# BalconyLight.net
KiCad netlist of a schematic drawn in EAGLE
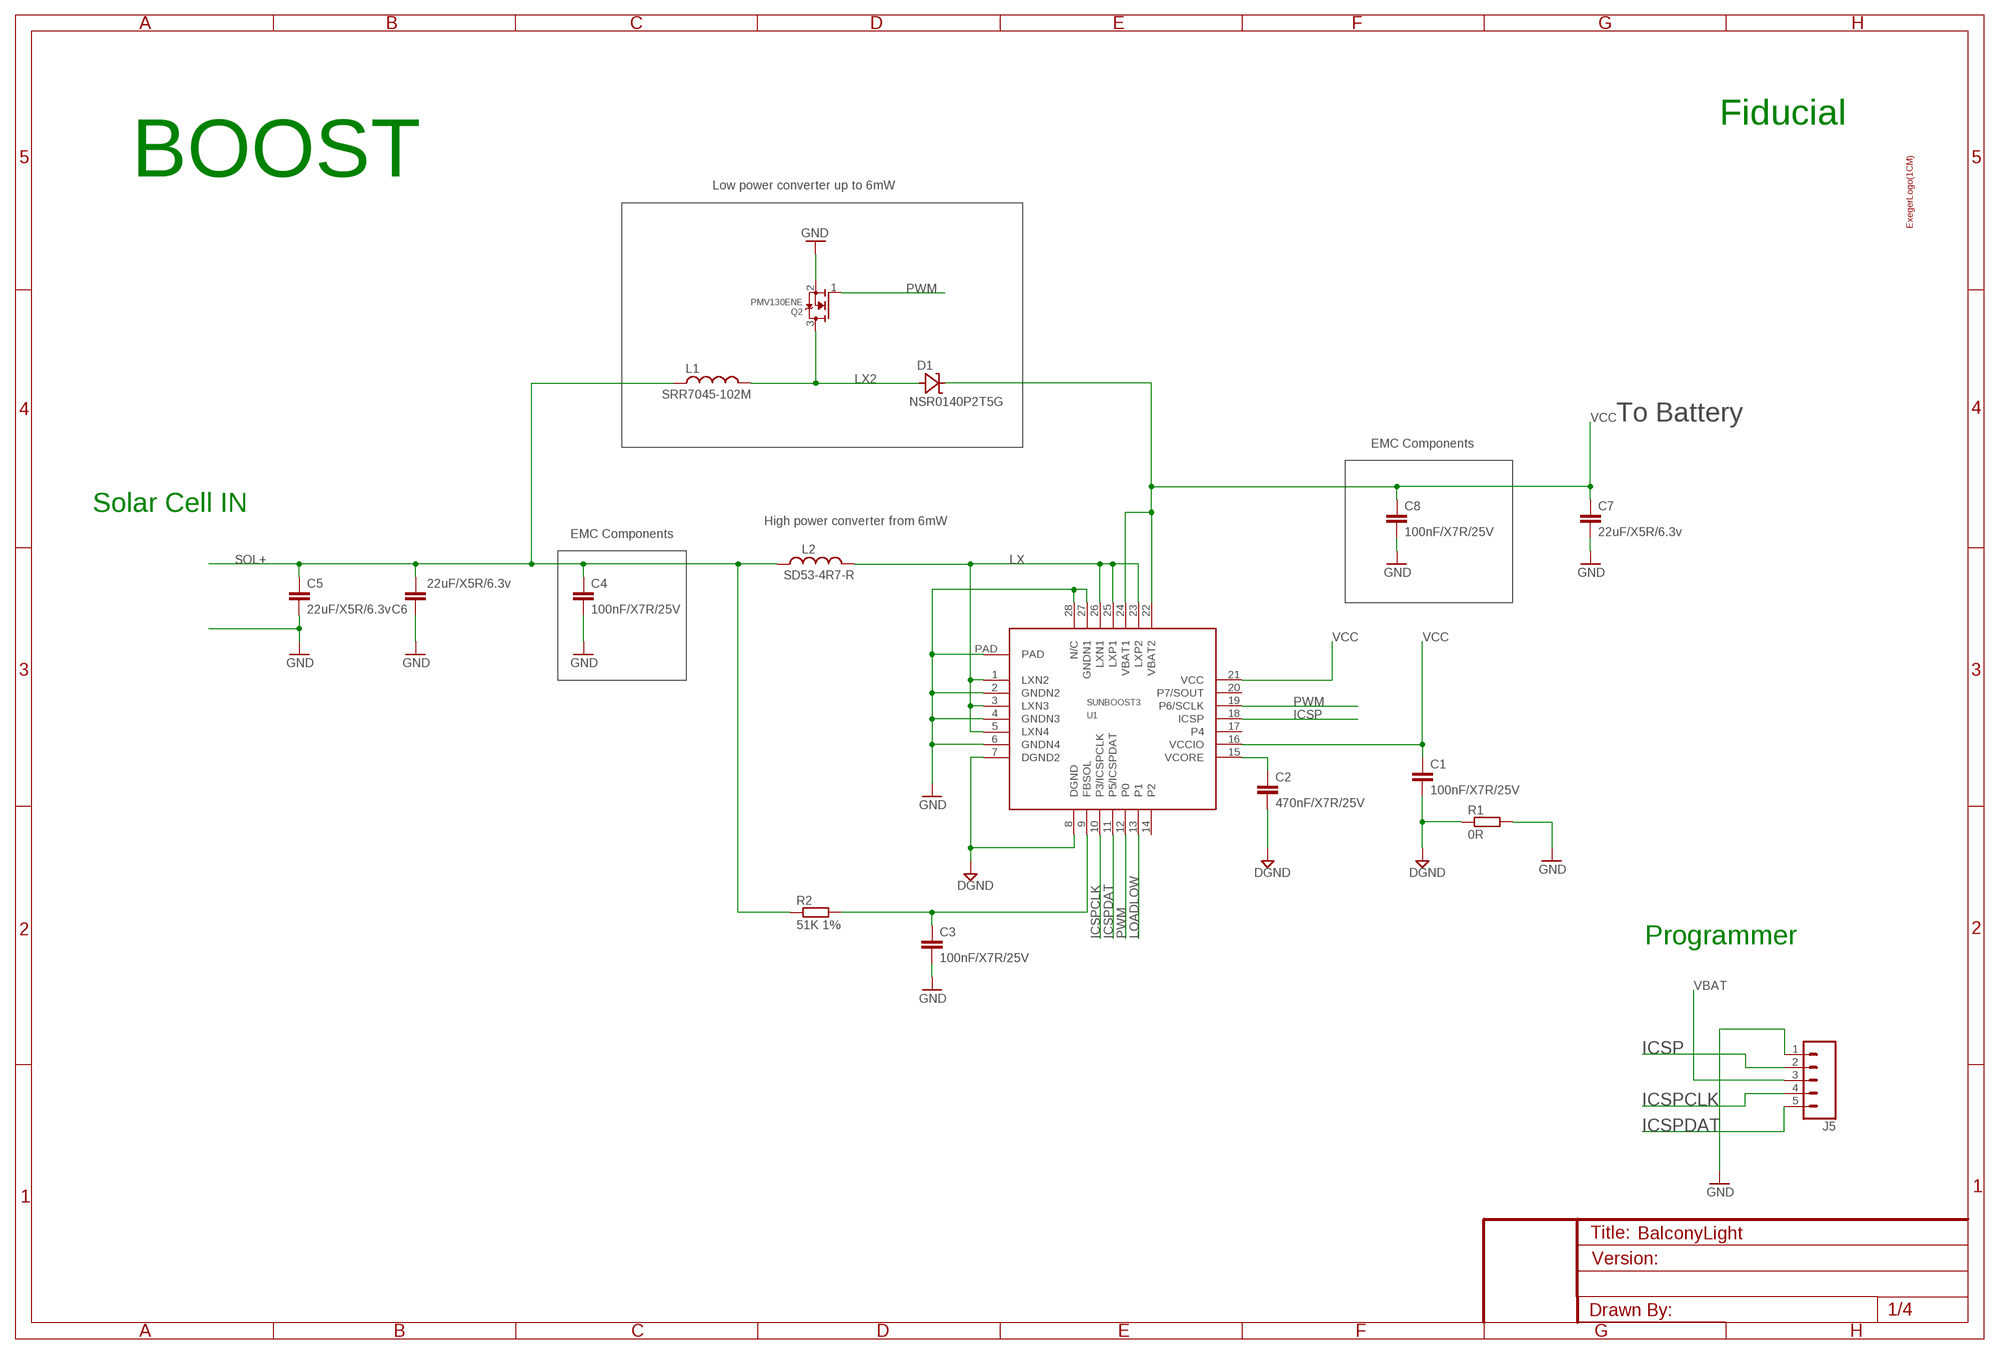
[diagram p0: schematic, sheet 1]
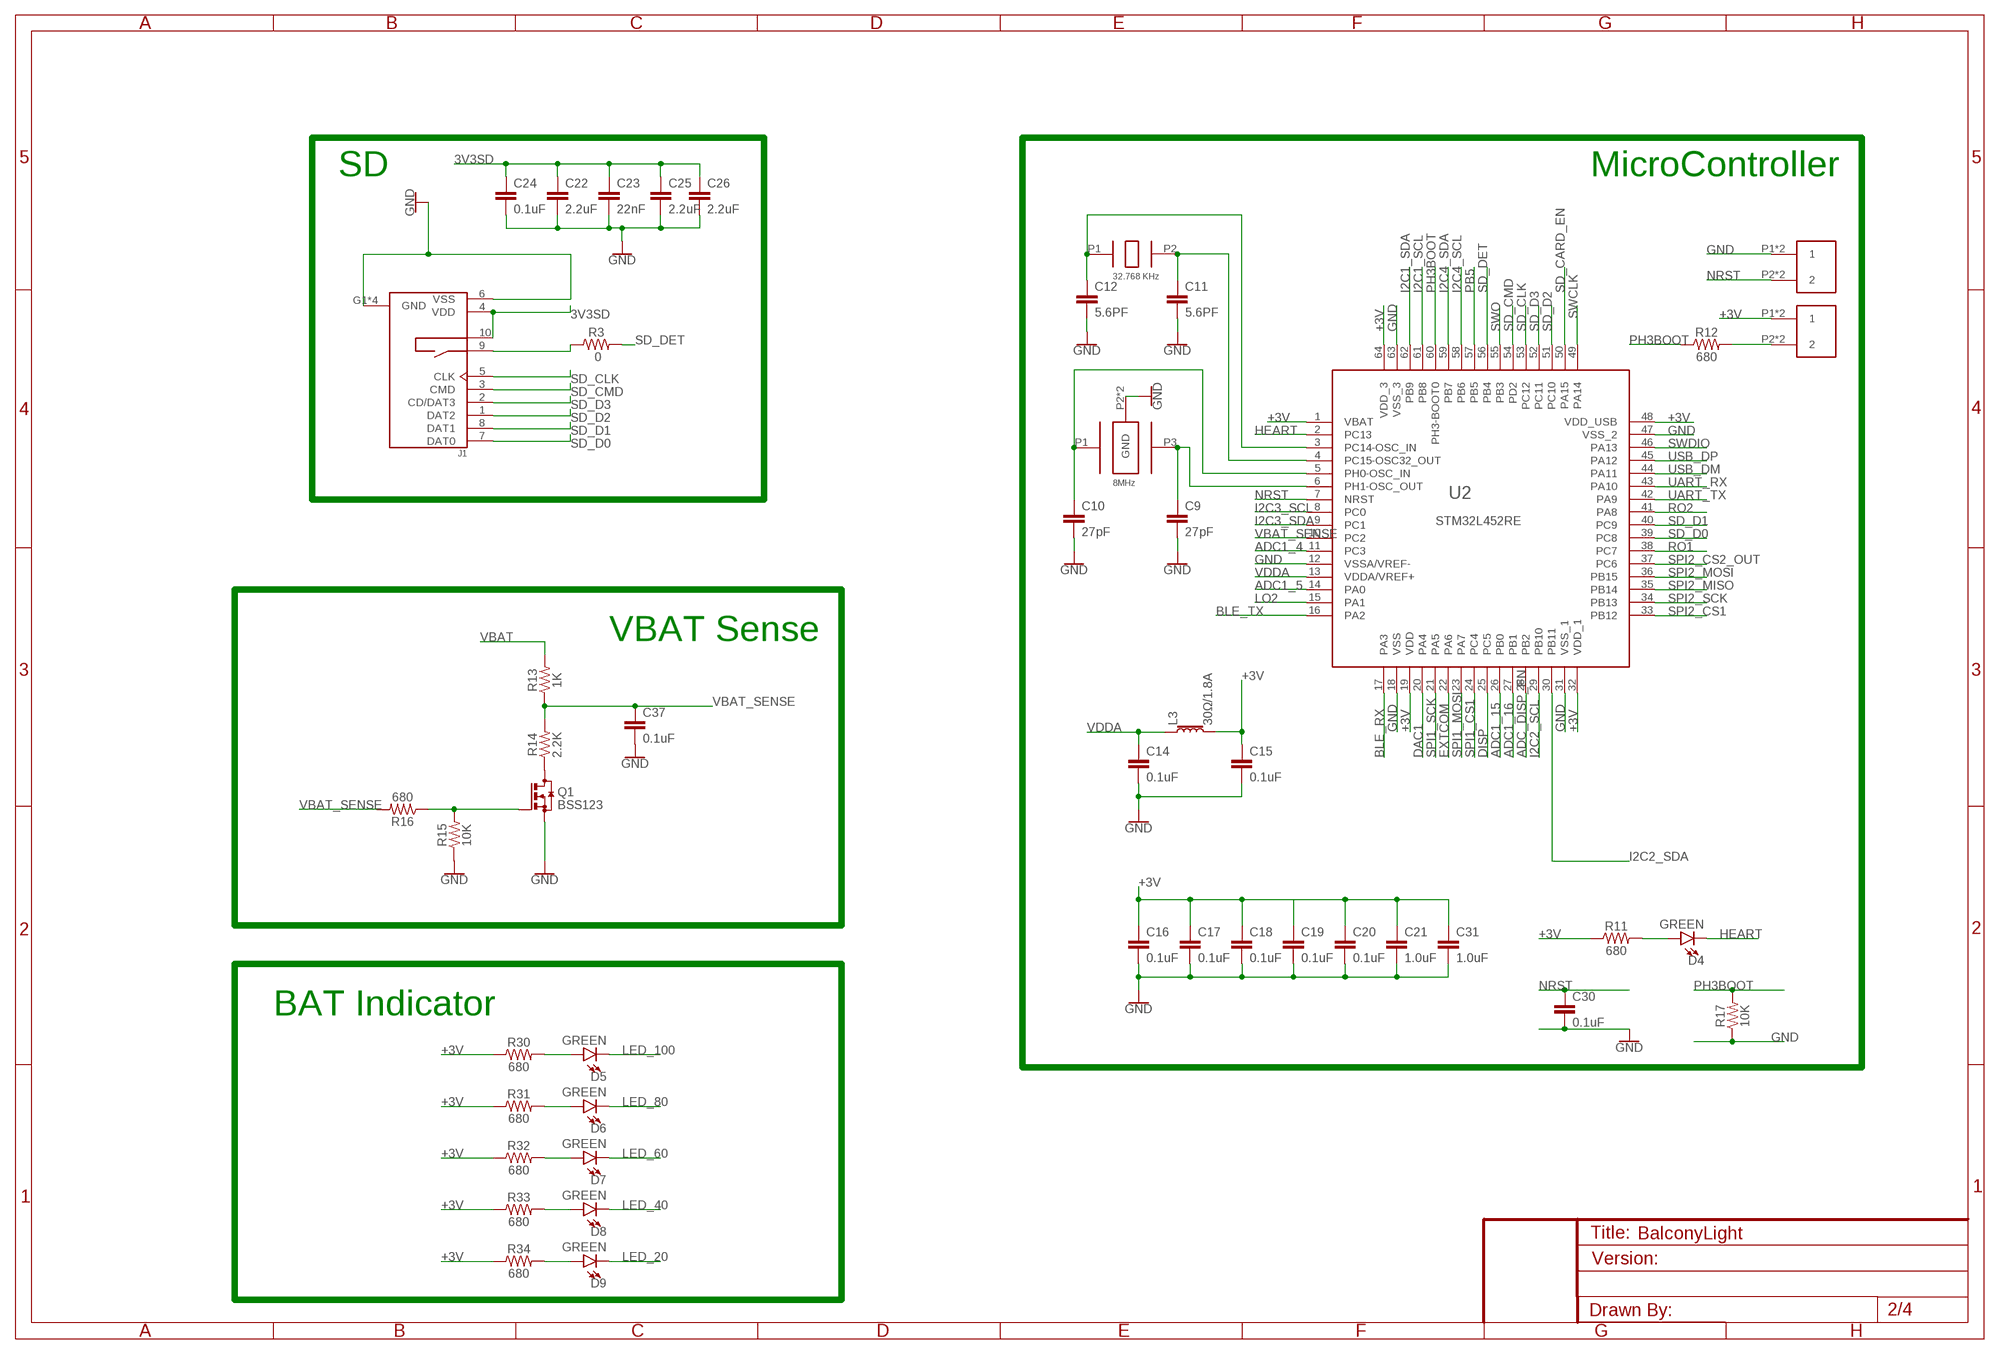
[diagram p1: schematic, sheet 2]
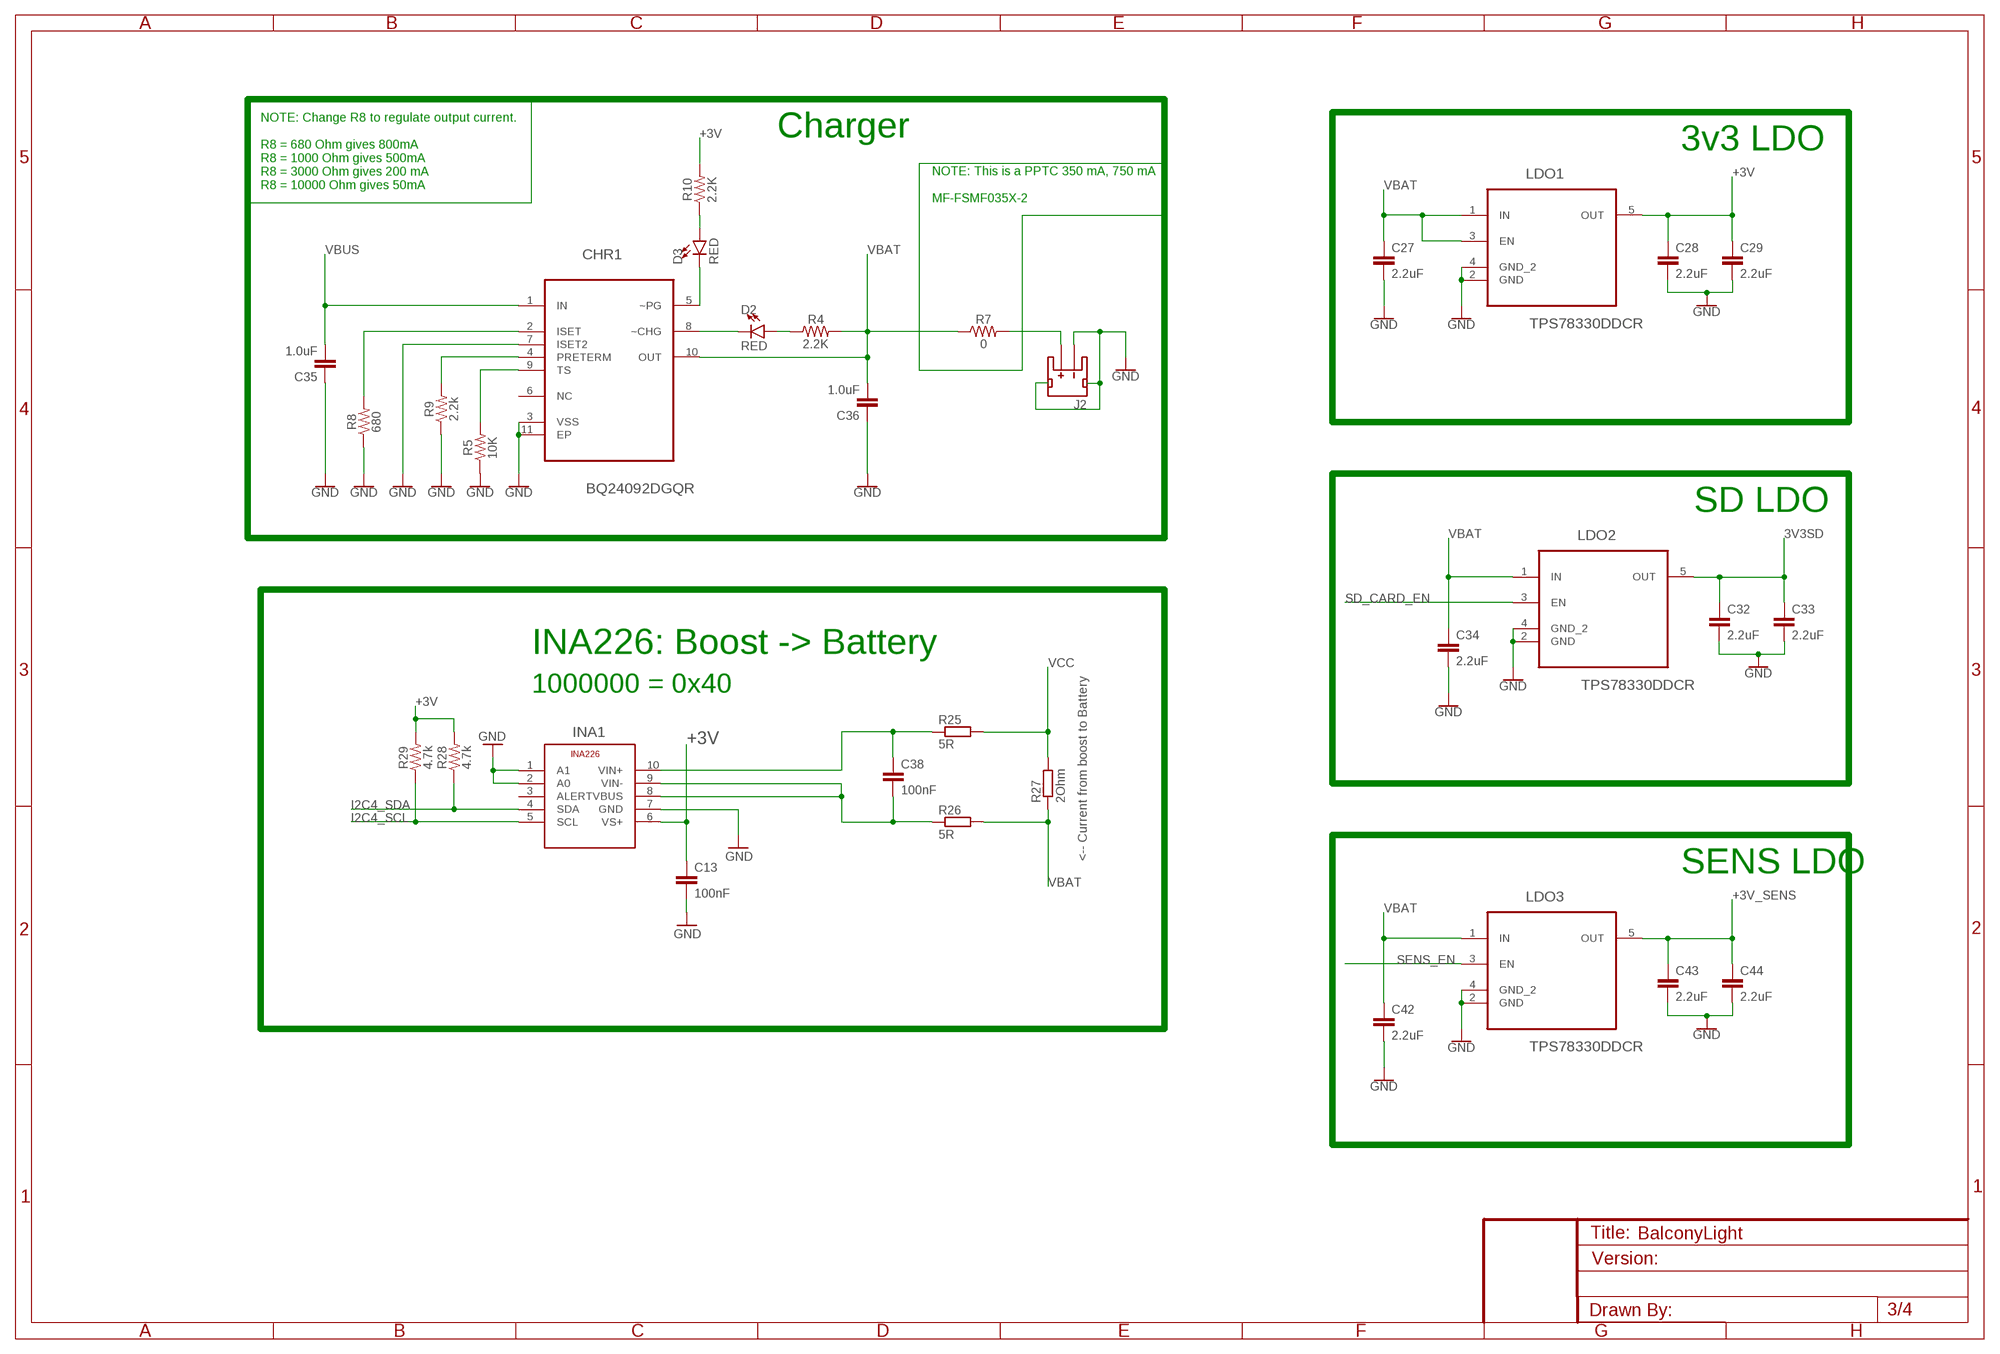
[diagram p2: schematic, sheet 3]
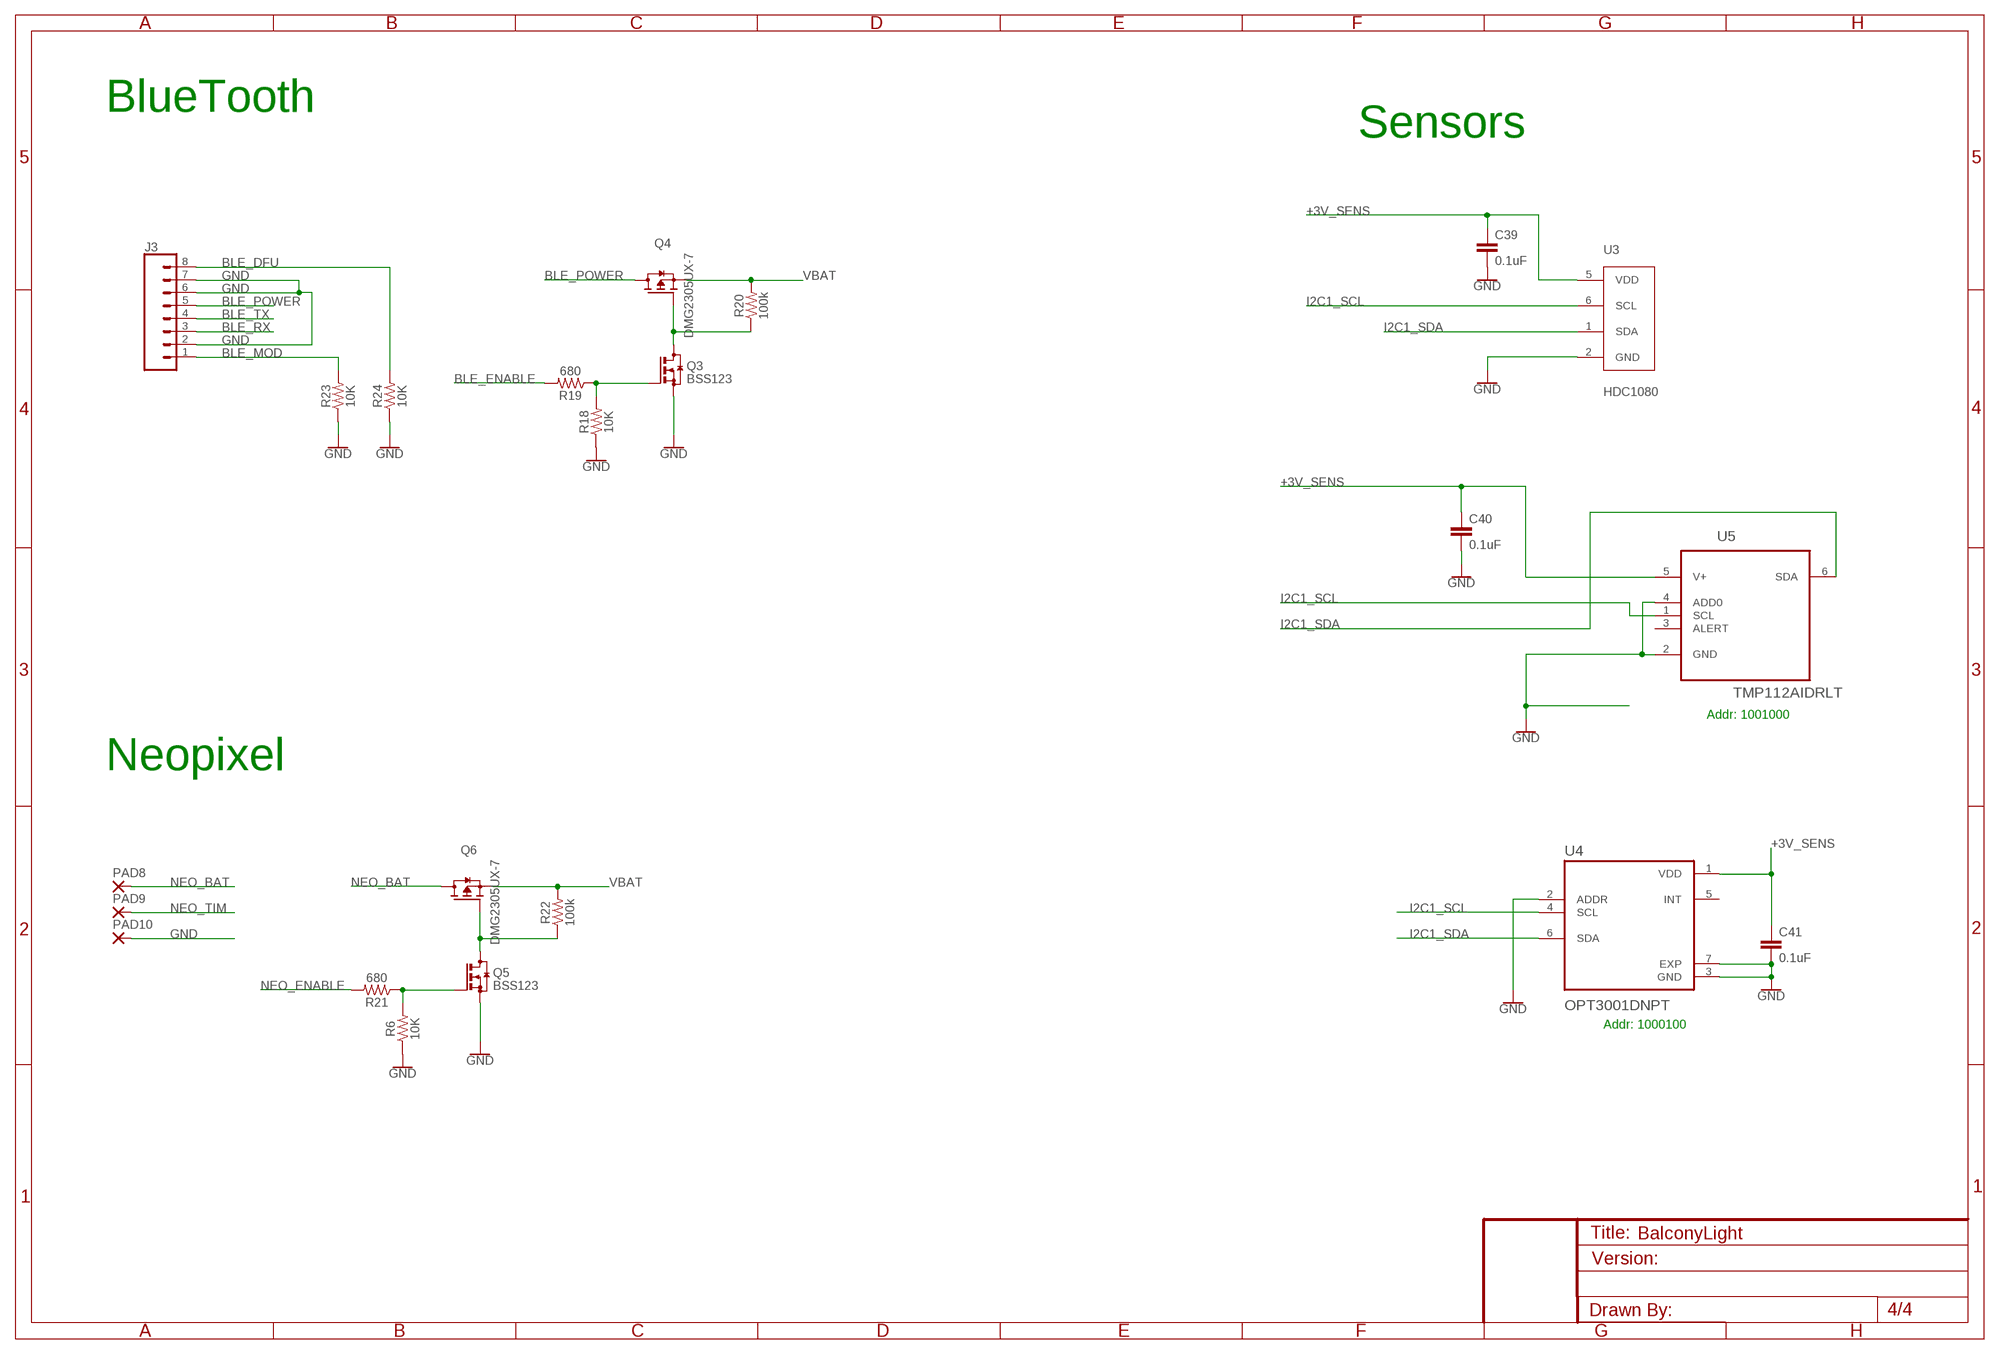
[diagram p3: schematic, sheet 4]

(export (version "E")
  (design (tool "Eeschema 10.0.6"))
  (components
    (comp (ref "C13")
      (value "100nF")
      (footprint "eagle-import:C0402")
      (libsource (lib "eagle-import") (part "C-EUC0402"))
    )
    (comp (ref "C27")
      (value "2.2uF")
      (footprint "eagle-import:0603")
      (libsource (lib "eagle-import") (part "2.2UF-0603-10V-20%"))
    )
    (comp (ref "C28")
      (value "2.2uF")
      (footprint "eagle-import:0603")
      (libsource (lib "eagle-import") (part "2.2UF-0603-10V-20%"))
    )
    (comp (ref "C29")
      (value "2.2uF")
      (footprint "eagle-import:0603")
      (libsource (lib "eagle-import") (part "2.2UF-0603-10V-20%"))
    )
    (comp (ref "C32")
      (value "2.2uF")
      (footprint "eagle-import:0603")
      (libsource (lib "eagle-import") (part "2.2UF-0603-10V-20%"))
    )
    (comp (ref "C33")
      (value "2.2uF")
      (footprint "eagle-import:0603")
      (libsource (lib "eagle-import") (part "2.2UF-0603-10V-20%"))
    )
    (comp (ref "C34")
      (value "2.2uF")
      (footprint "eagle-import:0603")
      (libsource (lib "eagle-import") (part "2.2UF-0603-10V-20%"))
    )
    (comp (ref "C35")
      (value "1.0uF")
      (footprint "eagle-import:0603")
      (libsource (lib "eagle-import") (part "1.0UF-0603-16V-10%"))
    )
    (comp (ref "C36")
      (value "1.0uF")
      (footprint "eagle-import:0603")
      (libsource (lib "eagle-import") (part "1.0UF-0603-16V-10%"))
    )
    (comp (ref "C38")
      (value "100nF")
      (footprint "eagle-import:C0402")
      (libsource (lib "eagle-import") (part "C-EUC0402"))
    )
    (comp (ref "C42")
      (value "2.2uF")
      (footprint "eagle-import:0603")
      (libsource (lib "eagle-import") (part "2.2UF-0603-10V-20%"))
    )
    (comp (ref "C43")
      (value "2.2uF")
      (footprint "eagle-import:0603")
      (libsource (lib "eagle-import") (part "2.2UF-0603-10V-20%"))
    )
    (comp (ref "C44")
      (value "2.2uF")
      (footprint "eagle-import:0603")
      (libsource (lib "eagle-import") (part "2.2UF-0603-10V-20%"))
    )
    (comp (ref "CHR1")
      (value "BQ24092DGQR")
      (footprint "eagle-import:SOP50P490X110-11N")
      (fields (field (name "MF") "Texas Instruments"))
      (libsource (lib "eagle-import") (part "BQ24092DGQR"))
    )
    (comp (ref "D2")
      (value "RED")
      (footprint "eagle-import:LED-0603")
      (libsource (lib "eagle-import") (part "LED-RED0603"))
    )
    (comp (ref "D3")
      (value "RED")
      (footprint "eagle-import:LED-0603")
      (libsource (lib "eagle-import") (part "LED-RED0603"))
    )
    (comp (ref "INA1")
      (value "TI-INA226")
      (footprint "eagle-import:TI-INA226")
      (libsource (lib "eagle-import") (part "TI-INA226"))
    )
    (comp (ref "J2")
      (value "JST_2MM_MALE")
      (footprint "eagle-import:JST-2-SMD")
      (libsource (lib "eagle-import") (part "JST_2MM_MALE"))
    )
    (comp (ref "LDO1")
      (value "TPS78330DDCR")
      (footprint "eagle-import:SOT95P280X110-5N")
      (fields (field (name "MF") "Texas Instruments"))
      (libsource (lib "eagle-import") (part "TPS78330DDCR"))
    )
    (comp (ref "LDO2")
      (value "TPS78330DDCR")
      (footprint "eagle-import:SOT95P280X110-5N")
      (fields (field (name "MF") "Texas Instruments"))
      (libsource (lib "eagle-import") (part "TPS78330DDCR"))
    )
    (comp (ref "LDO3")
      (value "TPS78330DDCR")
      (footprint "eagle-import:SOT95P280X110-5N")
      (fields (field (name "MF") "Texas Instruments"))
      (libsource (lib "eagle-import") (part "TPS78330DDCR"))
    )
    (comp (ref "R4")
      (value "2.2K")
      (footprint "eagle-import:0402")
      (libsource (lib "eagle-import") (part "100KOHM-0402-1/16W-1%"))
    )
    (comp (ref "R5")
      (value "10K")
      (footprint "eagle-import:0402")
      (libsource (lib "eagle-import") (part "100KOHM-0402-1/16W-1%"))
    )
    (comp (ref "R7")
      (value "0")
      (footprint "eagle-import:0603")
      (libsource (lib "eagle-import") (part "0OHM-0603-1/10W-5%"))
    )
    (comp (ref "R8")
      (value "680")
      (footprint "eagle-import:0402")
      (libsource (lib "eagle-import") (part "100KOHM-0402-1/16W-1%"))
    )
    (comp (ref "R9")
      (value "2.2k")
      (footprint "eagle-import:0402")
      (libsource (lib "eagle-import") (part "100KOHM-0402-1/16W-1%"))
    )
    (comp (ref "R10")
      (value "2.2K")
      (footprint "eagle-import:0402")
      (libsource (lib "eagle-import") (part "100KOHM-0402-1/16W-1%"))
    )
    (comp (ref "R25")
      (value "5R")
      (footprint "eagle-import:R0402")
      (libsource (lib "eagle-import") (part "R-EU_R0402"))
    )
    (comp (ref "R26")
      (value "5R")
      (footprint "eagle-import:R0402")
      (libsource (lib "eagle-import") (part "R-EU_R0402"))
    )
    (comp (ref "R27")
      (value "2Ohm")
      (footprint "eagle-import:R0603")
      (libsource (lib "eagle-import") (part "R-EU_R0603"))
    )
    (comp (ref "R28")
      (value "4.7k")
      (footprint "eagle-import:0603")
      (libsource (lib "eagle-import") (part "4.7KOHM-0603-1/10W-1%"))
    )
    (comp (ref "R29")
      (value "4.7k")
      (footprint "eagle-import:0603")
      (libsource (lib "eagle-import") (part "4.7KOHM-0603-1/10W-1%"))
    )
    (comp (ref "C1")
      (value "100nF/X7R/25V")
      (footprint "eagle-import:C0402")
      (libsource (lib "eagle-import") (part "C-EUC0402"))
    )
    (comp (ref "C2")
      (value "470nF/X7R/25V")
      (footprint "eagle-import:C0402")
      (libsource (lib "eagle-import") (part "C-EUC0402"))
    )
    (comp (ref "C3")
      (value "100nF/X7R/25V")
      (footprint "eagle-import:C0402")
      (libsource (lib "eagle-import") (part "C-EUC0402"))
    )
    (comp (ref "C4")
      (value "100nF/X7R/25V")
      (footprint "eagle-import:C0402")
      (libsource (lib "eagle-import") (part "C-EUC0402"))
    )
    (comp (ref "C5")
      (value "22uF/X5R/6.3v")
      (footprint "eagle-import:C0805")
      (libsource (lib "eagle-import") (part "C-EUC0805"))
    )
    (comp (ref "C6")
      (value "22uF/X5R/6.3v")
      (footprint "eagle-import:C0805")
      (libsource (lib "eagle-import") (part "C-EUC0805"))
    )
    (comp (ref "C7")
      (value "22uF/X5R/6.3v")
      (footprint "eagle-import:C0805")
      (libsource (lib "eagle-import") (part "C-EUC0805"))
    )
    (comp (ref "C8")
      (value "100nF/X7R/25V")
      (footprint "eagle-import:C0402")
      (libsource (lib "eagle-import") (part "C-EUC0402"))
    )
    (comp (ref "D1")
      (value "NSR0140P2T5G")
      (footprint "eagle-import:SODFL1006X40N")
      (libsource (lib "eagle-import") (part "NSR0140P2T5G"))
    )
    (comp (ref "J5")
      (value "CONN_05LOCK")
      (footprint "eagle-import:1X05_LOCK")
      (libsource (lib "eagle-import") (part "CONN_05LOCK"))
    )
    (comp (ref "L1")
      (value "SRR7045-102M")
      (footprint "eagle-import:SRR7045")
      (libsource (lib "eagle-import") (part "SRR7045-102M"))
    )
    (comp (ref "L2")
      (value "SD53-4R7-R")
      (footprint "eagle-import:SD53")
      (libsource (lib "eagle-import") (part "SD53-4R7-R"))
    )
    (comp (ref "Q2")
      (value "PMV130ENE")
      (footprint "eagle-import:SOT23")
      (libsource (lib "eagle-import") (part "MOSFET-NREFLOW"))
    )
    (comp (ref "R1")
      (value "0R")
      (footprint "eagle-import:R0402")
      (libsource (lib "eagle-import") (part "resistor_R-EU_R0402"))
    )
    (comp (ref "R2")
      (value "51K 1%")
      (footprint "eagle-import:R0402")
      (libsource (lib "eagle-import") (part "resistor_R-EU_R0402"))
    )
    (comp (ref "U$13")
      (value "EXEGER_LOGO_1CM")
      (footprint "eagle-import:EXEGER_LOGO_1CM")
      (libsource (lib "eagle-import") (part "EXEGER_LOGO_1CM"))
    )
    (comp (ref "U1")
      (value "SUNBOOST3")
      (footprint "eagle-import:QFN-28-4X4")
      (libsource (lib "eagle-import") (part "SUNBOOST3"))
    )
    (comp (ref "C9")
      (value "27pF")
      (footprint "eagle-import:0402")
      (libsource (lib "eagle-import") (part "0.8PF-0402-50V-0.1PF"))
    )
    (comp (ref "C10")
      (value "27pF")
      (footprint "eagle-import:0402")
      (libsource (lib "eagle-import") (part "0.8PF-0402-50V-0.1PF"))
    )
    (comp (ref "C11")
      (value "5.6PF")
      (footprint "eagle-import:0603")
      (libsource (lib "eagle-import") (part "5.6PF-0603-50V-5%"))
    )
    (comp (ref "C12")
      (value "5.6PF")
      (footprint "eagle-import:0603")
      (libsource (lib "eagle-import") (part "5.6PF-0603-50V-5%"))
    )
    (comp (ref "C14")
      (value "0.1uF")
      (footprint "eagle-import:0402")
      (libsource (lib "eagle-import") (part "0.1UF-0402-16V-10%"))
    )
    (comp (ref "C15")
      (value "0.1uF")
      (footprint "eagle-import:0402")
      (libsource (lib "eagle-import") (part "0.1UF-0402-16V-10%"))
    )
    (comp (ref "C16")
      (value "0.1uF")
      (footprint "eagle-import:0402")
      (libsource (lib "eagle-import") (part "0.1UF-0402-16V-10%"))
    )
    (comp (ref "C17")
      (value "0.1uF")
      (footprint "eagle-import:0402")
      (libsource (lib "eagle-import") (part "0.1UF-0402-16V-10%"))
    )
    (comp (ref "C18")
      (value "0.1uF")
      (footprint "eagle-import:0402")
      (libsource (lib "eagle-import") (part "0.1UF-0402-16V-10%"))
    )
    (comp (ref "C19")
      (value "0.1uF")
      (footprint "eagle-import:0402")
      (libsource (lib "eagle-import") (part "0.1UF-0402-16V-10%"))
    )
    (comp (ref "C20")
      (value "0.1uF")
      (footprint "eagle-import:0402")
      (libsource (lib "eagle-import") (part "0.1UF-0402-16V-10%"))
    )
    (comp (ref "C21")
      (value "1.0uF")
      (footprint "eagle-import:0603")
      (libsource (lib "eagle-import") (part "1.0UF-0603-16V-10%"))
    )
    (comp (ref "C22")
      (value "2.2uF")
      (footprint "eagle-import:0603")
      (libsource (lib "eagle-import") (part "2.2UF-0603-10V-20%"))
    )
    (comp (ref "C23")
      (value "22nF")
      (footprint "eagle-import:0603")
      (libsource (lib "eagle-import") (part "22NF/22,000PF-0603-50V-10%"))
    )
    (comp (ref "C24")
      (value "0.1uF")
      (footprint "eagle-import:0603")
      (libsource (lib "eagle-import") (part "0.1UF-0603-25V-(+80/-20%)"))
    )
    (comp (ref "C25")
      (value "2.2uF")
      (footprint "eagle-import:0603")
      (libsource (lib "eagle-import") (part "2.2UF-0603-10V-20%"))
    )
    (comp (ref "C26")
      (value "2.2uF")
      (footprint "eagle-import:0603")
      (libsource (lib "eagle-import") (part "2.2UF-0603-10V-20%"))
    )
    (comp (ref "C30")
      (value "0.1uF")
      (footprint "eagle-import:0402")
      (libsource (lib "eagle-import") (part "0.1UF-0402-16V-10%"))
    )
    (comp (ref "C31")
      (value "1.0uF")
      (footprint "eagle-import:0603")
      (libsource (lib "eagle-import") (part "1.0UF-0603-16V-10%"))
    )
    (comp (ref "C37")
      (value "0.1uF")
      (footprint "eagle-import:0402")
      (libsource (lib "eagle-import") (part "0.1UF-0402-16V-10%"))
    )
    (comp (ref "D4")
      (value "GREEN")
      (footprint "eagle-import:LED-0603")
      (libsource (lib "eagle-import") (part "LED-GREEN0603"))
    )
    (comp (ref "D5")
      (value "GREEN")
      (footprint "eagle-import:LED-0603")
      (libsource (lib "eagle-import") (part "LED-GREEN0603"))
    )
    (comp (ref "D6")
      (value "GREEN")
      (footprint "eagle-import:LED-0603")
      (libsource (lib "eagle-import") (part "LED-GREEN0603"))
    )
    (comp (ref "D7")
      (value "GREEN")
      (footprint "eagle-import:LED-0603")
      (libsource (lib "eagle-import") (part "LED-GREEN0603"))
    )
    (comp (ref "D8")
      (value "GREEN")
      (footprint "eagle-import:LED-0603")
      (libsource (lib "eagle-import") (part "LED-GREEN0603"))
    )
    (comp (ref "D9")
      (value "GREEN")
      (footprint "eagle-import:LED-0603")
      (libsource (lib "eagle-import") (part "LED-GREEN0603"))
    )
    (comp (ref "J1")
      (value "104031-0811")
      (footprint "eagle-import:MOLEX_104031-0811")
      (fields (field (name "MF") "Molex, LLC"))
      (libsource (lib "eagle-import") (part "104031-0811"))
    )
    (comp (ref "L3")
      (value "30Ω/1.8A")
      (footprint "eagle-import:0603")
      (libsource (lib "eagle-import") (part "FERRITE_BEAD-0603"))
    )
    (comp (ref "OSC1")
      (value "OSC_32.768_KHZ")
      (footprint "eagle-import:OSC_32.768_KHZ")
      (libsource (lib "eagle-import") (part "OSC_32.768_KHZ"))
    )
    (comp (ref "Q1")
      (value "BSS123")
      (footprint "eagle-import:SOT23")
      (libsource (lib "eagle-import") (part "BSS123"))
    )
    (comp (ref "R3")
      (value "0")
      (footprint "eagle-import:0402")
      (libsource (lib "eagle-import") (part "RESISTOR0402"))
    )
    (comp (ref "R11")
      (value "680")
      (footprint "eagle-import:0402")
      (libsource (lib "eagle-import") (part "100KOHM-0402-1/16W-1%"))
    )
    (comp (ref "R12")
      (value "680")
      (footprint "eagle-import:0402")
      (libsource (lib "eagle-import") (part "100KOHM-0402-1/16W-1%"))
    )
    (comp (ref "R13")
      (value "1K")
      (footprint "eagle-import:0402")
      (libsource (lib "eagle-import") (part "100KOHM-0402-1/16W-1%"))
    )
    (comp (ref "R14")
      (value "2.2K")
      (footprint "eagle-import:0402")
      (libsource (lib "eagle-import") (part "100KOHM-0402-1/16W-1%"))
    )
    (comp (ref "R15")
      (value "10K")
      (footprint "eagle-import:0402")
      (libsource (lib "eagle-import") (part "100KOHM-0402-1/16W-1%"))
    )
    (comp (ref "R16")
      (value "680")
      (footprint "eagle-import:0402")
      (libsource (lib "eagle-import") (part "100KOHM-0402-1/16W-1%"))
    )
    (comp (ref "R17")
      (value "10K")
      (footprint "eagle-import:0402")
      (libsource (lib "eagle-import") (part "100KOHM-0402-1/16W-1%"))
    )
    (comp (ref "R30")
      (value "680")
      (footprint "eagle-import:0402")
      (libsource (lib "eagle-import") (part "100KOHM-0402-1/16W-1%"))
    )
    (comp (ref "R31")
      (value "680")
      (footprint "eagle-import:0402")
      (libsource (lib "eagle-import") (part "100KOHM-0402-1/16W-1%"))
    )
    (comp (ref "R32")
      (value "680")
      (footprint "eagle-import:0402")
      (libsource (lib "eagle-import") (part "100KOHM-0402-1/16W-1%"))
    )
    (comp (ref "R33")
      (value "680")
      (footprint "eagle-import:0402")
      (libsource (lib "eagle-import") (part "100KOHM-0402-1/16W-1%"))
    )
    (comp (ref "R34")
      (value "680")
      (footprint "eagle-import:0402")
      (libsource (lib "eagle-import") (part "100KOHM-0402-1/16W-1%"))
    )
    (comp (ref "S1")
      (value "EVQ-P7J")
      (footprint "eagle-import:EVQ-P7J")
      (libsource (lib "eagle-import") (part "EVQ-P7J"))
    )
    (comp (ref "S2")
      (value "EVQ-P7J")
      (footprint "eagle-import:EVQ-P7J")
      (libsource (lib "eagle-import") (part "EVQ-P7J"))
    )
    (comp (ref "U$2")
      (value "OSC_8_MHZ")
      (footprint "eagle-import:OSC_8_MHZ")
      (libsource (lib "eagle-import") (part "OSC_8_MHZ"))
    )
    (comp (ref "U2")
      (value "STM32L452RE")
      (footprint "eagle-import:TQFP64")
      (libsource (lib "eagle-import") (part "STM32L452RE"))
    )
    (comp (ref "C39")
      (value "0.1uF")
      (footprint "eagle-import:0603")
      (libsource (lib "eagle-import") (part "0.1UF-0603-25V-(+80/-20%)"))
    )
    (comp (ref "C40")
      (value "0.1uF")
      (footprint "eagle-import:0603")
      (libsource (lib "eagle-import") (part "0.1UF-0603-25V-(+80/-20%)"))
    )
    (comp (ref "C41")
      (value "0.1uF")
      (footprint "eagle-import:0603")
      (libsource (lib "eagle-import") (part "0.1UF-0603-25V-(+80/-20%)"))
    )
    (comp (ref "J3")
      (value "CONN_08FEMALE_LOCK")
      (footprint "eagle-import:1X08_FEMALE_LOCK")
      (libsource (lib "eagle-import") (part "CONN_08FEMALE_LOCK"))
    )
    (comp (ref "PAD8")
      (value "SMD5")
      (footprint "eagle-import:SMD2,54-5,08")
      (libsource (lib "eagle-import") (part "SMD5"))
    )
    (comp (ref "PAD9")
      (value "SMD5")
      (footprint "eagle-import:SMD2,54-5,08")
      (libsource (lib "eagle-import") (part "SMD5"))
    )
    (comp (ref "PAD10")
      (value "SMD5")
      (footprint "eagle-import:SMD2,54-5,08")
      (libsource (lib "eagle-import") (part "SMD5"))
    )
    (comp (ref "Q3")
      (value "BSS123")
      (footprint "eagle-import:SOT23")
      (libsource (lib "eagle-import") (part "BSS123"))
    )
    (comp (ref "Q4")
      (value "DMG2305UX-7")
      (footprint "eagle-import:SOT91P240X110-3N_DMG2305UX-7")
      (fields (field (name "MF") "Diodes Inc."))
      (libsource (lib "eagle-import") (part "DMG2305UX-7"))
    )
    (comp (ref "Q5")
      (value "BSS123")
      (footprint "eagle-import:SOT23")
      (libsource (lib "eagle-import") (part "BSS123"))
    )
    (comp (ref "Q6")
      (value "DMG2305UX-7")
      (footprint "eagle-import:SOT91P240X110-3N_DMG2305UX-7")
      (fields (field (name "MF") "Diodes Inc."))
      (libsource (lib "eagle-import") (part "DMG2305UX-7"))
    )
    (comp (ref "R6")
      (value "10K")
      (footprint "eagle-import:0402")
      (libsource (lib "eagle-import") (part "100KOHM-0402-1/16W-1%"))
    )
    (comp (ref "R18")
      (value "10K")
      (footprint "eagle-import:0402")
      (libsource (lib "eagle-import") (part "100KOHM-0402-1/16W-1%"))
    )
    (comp (ref "R19")
      (value "680")
      (footprint "eagle-import:0402")
      (libsource (lib "eagle-import") (part "100KOHM-0402-1/16W-1%"))
    )
    (comp (ref "R20")
      (value "100k")
      (footprint "eagle-import:0603")
      (libsource (lib "eagle-import") (part "100KOHM-0603-1/10W-1%"))
    )
    (comp (ref "R21")
      (value "680")
      (footprint "eagle-import:0402")
      (libsource (lib "eagle-import") (part "100KOHM-0402-1/16W-1%"))
    )
    (comp (ref "R22")
      (value "100k")
      (footprint "eagle-import:0603")
      (libsource (lib "eagle-import") (part "100KOHM-0603-1/10W-1%"))
    )
    (comp (ref "R23")
      (value "10K")
      (footprint "eagle-import:0402")
      (libsource (lib "eagle-import") (part "100KOHM-0402-1/16W-1%"))
    )
    (comp (ref "R24")
      (value "10K")
      (footprint "eagle-import:0402")
      (libsource (lib "eagle-import") (part "100KOHM-0402-1/16W-1%"))
    )
    (comp (ref "U3")
      (value "HDC1080")
      (footprint "eagle-import:HDC1080")
      (libsource (lib "eagle-import") (part "HDC1080"))
    )
    (comp (ref "U4")
      (value "OPT3001DNPT")
      (footprint "eagle-import:SON65P200X200X65-7N")
      (fields (field (name "MF") "Texas Instruments"))
      (libsource (lib "eagle-import") (part "OPT3001DNPT"))
    )
    (comp (ref "U5")
      (value "TMP112AIDRLT")
      (footprint "eagle-import:SOT50P120X60-6N")
      (fields (field (name "MF") "Texas Instruments"))
      (libsource (lib "eagle-import") (part "TMP112AIDRLT"))
    )
  )
  (nets
    (net (code "1") (name "+3V") (class "Default")
      (node (ref "C13") (pin "1") (pinfunction "1_1") (pintype "passive"))
      (node (ref "C15") (pin "1") (pinfunction "1_1") (pintype "passive"))
      (node (ref "C16") (pin "1") (pinfunction "1_1") (pintype "passive"))
      (node (ref "C17") (pin "1") (pinfunction "1_1") (pintype "passive"))
      (node (ref "C18") (pin "1") (pinfunction "1_1") (pintype "passive"))
      (node (ref "C19") (pin "1") (pinfunction "1_1") (pintype "passive"))
      (node (ref "C20") (pin "1") (pinfunction "1_1") (pintype "passive"))
      (node (ref "C21") (pin "1") (pinfunction "1_1") (pintype "passive"))
      (node (ref "C28") (pin "1") (pinfunction "1_1") (pintype "passive"))
      (node (ref "C29") (pin "1") (pinfunction "1_1") (pintype "passive"))
      (node (ref "C31") (pin "1") (pinfunction "1_1") (pintype "passive"))
      (node (ref "INA1") (pin "6") (pinfunction "VS+_6") (pintype "bidirectional"))
      (node (ref "L3") (pin "2") (pinfunction "2_2") (pintype "passive"))
      (node (ref "LDO1") (pin "5") (pinfunction "OUT_5") (pintype "output"))
      (node (ref "R10") (pin "2") (pinfunction "2_2") (pintype "passive"))
      (node (ref "R11") (pin "1") (pinfunction "1_1") (pintype "passive"))
      (node (ref "R28") (pin "2") (pinfunction "2_2") (pintype "passive"))
      (node (ref "R29") (pin "2") (pinfunction "2_2") (pintype "passive"))
      (node (ref "R30") (pin "1") (pinfunction "1_1") (pintype "passive"))
      (node (ref "R31") (pin "1") (pinfunction "1_1") (pintype "passive"))
      (node (ref "R32") (pin "1") (pinfunction "1_1") (pintype "passive"))
      (node (ref "R33") (pin "1") (pinfunction "1_1") (pintype "passive"))
      (node (ref "R34") (pin "1") (pinfunction "1_1") (pintype "passive"))
      (node (ref "S2") (pin "P1") (pinfunction "1_P1") (pintype "bidirectional"))
      (node (ref "S2") (pin "P4") (pinfunction "1_P4") (pintype "bidirectional"))
      (node (ref "U2") (pin "1") (pinfunction "VBAT_1") (pintype "bidirectional"))
      (node (ref "U2") (pin "19") (pinfunction "VDD_19") (pintype "bidirectional"))
      (node (ref "U2") (pin "32") (pinfunction "VDD_1_32") (pintype "bidirectional"))
      (node (ref "U2") (pin "48") (pinfunction "VDD_USB_48") (pintype "bidirectional"))
      (node (ref "U2") (pin "64") (pinfunction "VDD_3_64") (pintype "bidirectional"))
    )
    (net (code "2") (name "+3V_SENS") (class "Default")
      (node (ref "C39") (pin "1") (pinfunction "1_1") (pintype "passive"))
      (node (ref "C40") (pin "1") (pinfunction "1_1") (pintype "passive"))
      (node (ref "C41") (pin "1") (pinfunction "1_1") (pintype "passive"))
      (node (ref "C43") (pin "1") (pinfunction "1_1") (pintype "passive"))
      (node (ref "C44") (pin "1") (pinfunction "1_1") (pintype "passive"))
      (node (ref "LDO3") (pin "5") (pinfunction "OUT_5") (pintype "output"))
      (node (ref "U3") (pin "5") (pinfunction "VDD_5") (pintype "bidirectional"))
      (node (ref "U4") (pin "1") (pinfunction "VDD_1") (pintype "power_in"))
      (node (ref "U5") (pin "5") (pinfunction "V+_5") (pintype "power_in"))
    )
    (net (code "3") (name "3V3SD") (class "Default")
      (node (ref "C22") (pin "1") (pinfunction "1_1") (pintype "passive"))
      (node (ref "C23") (pin "1") (pinfunction "1_1") (pintype "passive"))
      (node (ref "C24") (pin "1") (pinfunction "1_1") (pintype "passive"))
      (node (ref "C25") (pin "1") (pinfunction "1_1") (pintype "passive"))
      (node (ref "C26") (pin "1") (pinfunction "1_1") (pintype "passive"))
      (node (ref "C32") (pin "1") (pinfunction "1_1") (pintype "passive"))
      (node (ref "C33") (pin "1") (pinfunction "1_1") (pintype "passive"))
      (node (ref "J1") (pin "10") (pinfunction "CARD_DET2_10") (pintype "passive"))
      (node (ref "J1") (pin "4") (pinfunction "VDD_4") (pintype "power_in"))
      (node (ref "LDO2") (pin "5") (pinfunction "OUT_5") (pintype "output"))
    )
    (net (code "4") (name "ADC1_4") (class "Default")
      (node (ref "U2") (pin "11") (pinfunction "PC3_11") (pintype "bidirectional"))
    )
    (net (code "5") (name "ADC1_5") (class "Default")
      (node (ref "U2") (pin "14") (pinfunction "PA0_14") (pintype "bidirectional"))
    )
    (net (code "6") (name "ADC1_15") (class "Default")
      (node (ref "U2") (pin "26") (pinfunction "PB0_26") (pintype "bidirectional"))
    )
    (net (code "7") (name "ADC1_16") (class "Default")
      (node (ref "U2") (pin "27") (pinfunction "PB1_27") (pintype "bidirectional"))
    )
    (net (code "8") (name "ADC_DISP_EN") (class "Default")
      (node (ref "U2") (pin "28") (pinfunction "PB2_28") (pintype "bidirectional"))
    )
    (net (code "9") (name "BLE_DFU") (class "Default")
      (node (ref "J3") (pin "8") (pinfunction "8_8") (pintype "passive"))
      (node (ref "R24") (pin "2") (pinfunction "2_2") (pintype "passive"))
    )
    (net (code "10") (name "BLE_ENABLE") (class "Default")
      (node (ref "R19") (pin "2") (pinfunction "2_2") (pintype "passive"))
    )
    (net (code "11") (name "BLE_MOD") (class "Default")
      (node (ref "J3") (pin "1") (pinfunction "1_1") (pintype "passive"))
      (node (ref "R23") (pin "2") (pinfunction "2_2") (pintype "passive"))
    )
    (net (code "12") (name "BLE_POWER") (class "Default")
      (node (ref "J3") (pin "5") (pinfunction "5_5") (pintype "passive"))
      (node (ref "Q4") (pin "3") (pinfunction "D_3") (pintype "passive"))
    )
    (net (code "13") (name "BLE_RX") (class "Default")
      (node (ref "J3") (pin "3") (pinfunction "3_3") (pintype "passive"))
      (node (ref "U2") (pin "17") (pinfunction "PA3_17") (pintype "bidirectional"))
    )
    (net (code "14") (name "BLE_TX") (class "Default")
      (node (ref "J3") (pin "4") (pinfunction "4_4") (pintype "passive"))
      (node (ref "U2") (pin "16") (pinfunction "PA2_16") (pintype "bidirectional"))
    )
    (net (code "15") (name "DAC1") (class "Default")
      (node (ref "U2") (pin "20") (pinfunction "PA4_20") (pintype "bidirectional"))
    )
    (net (code "16") (name "DGND") (class "Default")
      (node (ref "C1") (pin "2") (pinfunction "2_2") (pintype "passive"))
      (node (ref "C2") (pin "2") (pinfunction "2_2") (pintype "passive"))
      (node (ref "R1") (pin "1") (pinfunction "1_1") (pintype "passive"))
      (node (ref "U1") (pin "7") (pinfunction "DGND2_7") (pintype "bidirectional"))
      (node (ref "U1") (pin "8") (pinfunction "DGND_8") (pintype "bidirectional"))
    )
    (net (code "17") (name "DISP") (class "Default")
      (node (ref "U2") (pin "25") (pinfunction "PC5_25") (pintype "bidirectional"))
    )
    (net (code "18") (name "EXTCOM") (class "Default")
      (node (ref "U2") (pin "22") (pinfunction "PA6_22") (pintype "bidirectional"))
    )
    (net (code "19") (name "GND") (class "Default")
      (node (ref "C10") (pin "2") (pinfunction "2_2") (pintype "passive"))
      (node (ref "C11") (pin "2") (pinfunction "2_2") (pintype "passive"))
      (node (ref "C12") (pin "2") (pinfunction "2_2") (pintype "passive"))
      (node (ref "C13") (pin "2") (pinfunction "2_2") (pintype "passive"))
      (node (ref "C14") (pin "2") (pinfunction "2_2") (pintype "passive"))
      (node (ref "C15") (pin "2") (pinfunction "2_2") (pintype "passive"))
      (node (ref "C16") (pin "2") (pinfunction "2_2") (pintype "passive"))
      (node (ref "C17") (pin "2") (pinfunction "2_2") (pintype "passive"))
      (node (ref "C18") (pin "2") (pinfunction "2_2") (pintype "passive"))
      (node (ref "C19") (pin "2") (pinfunction "2_2") (pintype "passive"))
      (node (ref "C20") (pin "2") (pinfunction "2_2") (pintype "passive"))
      (node (ref "C21") (pin "2") (pinfunction "2_2") (pintype "passive"))
      (node (ref "C22") (pin "2") (pinfunction "2_2") (pintype "passive"))
      (node (ref "C23") (pin "2") (pinfunction "2_2") (pintype "passive"))
      (node (ref "C24") (pin "2") (pinfunction "2_2") (pintype "passive"))
      (node (ref "C25") (pin "2") (pinfunction "2_2") (pintype "passive"))
      (node (ref "C26") (pin "2") (pinfunction "2_2") (pintype "passive"))
      (node (ref "C27") (pin "2") (pinfunction "2_2") (pintype "passive"))
      (node (ref "C28") (pin "2") (pinfunction "2_2") (pintype "passive"))
      (node (ref "C29") (pin "2") (pinfunction "2_2") (pintype "passive"))
      (node (ref "C3") (pin "2") (pinfunction "2_2") (pintype "passive"))
      (node (ref "C30") (pin "2") (pinfunction "2_2") (pintype "passive"))
      (node (ref "C31") (pin "2") (pinfunction "2_2") (pintype "passive"))
      (node (ref "C32") (pin "2") (pinfunction "2_2") (pintype "passive"))
      (node (ref "C33") (pin "2") (pinfunction "2_2") (pintype "passive"))
      (node (ref "C34") (pin "2") (pinfunction "2_2") (pintype "passive"))
      (node (ref "C35") (pin "1") (pinfunction "1_1") (pintype "passive"))
      (node (ref "C36") (pin "1") (pinfunction "1_1") (pintype "passive"))
      (node (ref "C37") (pin "2") (pinfunction "2_2") (pintype "passive"))
      (node (ref "C39") (pin "2") (pinfunction "2_2") (pintype "passive"))
      (node (ref "C4") (pin "2") (pinfunction "2_2") (pintype "passive"))
      (node (ref "C40") (pin "2") (pinfunction "2_2") (pintype "passive"))
      (node (ref "C41") (pin "2") (pinfunction "2_2") (pintype "passive"))
      (node (ref "C42") (pin "2") (pinfunction "2_2") (pintype "passive"))
      (node (ref "C43") (pin "2") (pinfunction "2_2") (pintype "passive"))
      (node (ref "C44") (pin "2") (pinfunction "2_2") (pintype "passive"))
      (node (ref "C5") (pin "2") (pinfunction "2_2") (pintype "passive"))
      (node (ref "C6") (pin "1") (pinfunction "1_1") (pintype "passive"))
      (node (ref "C7") (pin "2") (pinfunction "2_2") (pintype "passive"))
      (node (ref "C8") (pin "2") (pinfunction "2_2") (pintype "passive"))
      (node (ref "C9") (pin "2") (pinfunction "2_2") (pintype "passive"))
      (node (ref "CHR1") (pin "11") (pinfunction "EP_11") (pintype "passive"))
      (node (ref "CHR1") (pin "3") (pinfunction "VSS_3") (pintype "passive"))
      (node (ref "CHR1") (pin "7") (pinfunction "ISET2_7") (pintype "input"))
      (node (ref "INA1") (pin "1") (pinfunction "A1_1") (pintype "bidirectional"))
      (node (ref "INA1") (pin "2") (pinfunction "A0_2") (pintype "bidirectional"))
      (node (ref "INA1") (pin "7") (pinfunction "GND_7") (pintype "bidirectional"))
      (node (ref "J1") (pin "6") (pinfunction "VSS_6") (pintype "power_in"))
      (node (ref "J1") (pin "G1") (pinfunction "GND_G1") (pintype "power_in"))
      (node (ref "J1") (pin "G2") (pinfunction "GND_G2") (pintype "power_in"))
      (node (ref "J1") (pin "G3") (pinfunction "GND_G3") (pintype "power_in"))
      (node (ref "J1") (pin "G4") (pinfunction "GND_G4") (pintype "power_in"))
      (node (ref "J2") (pin "1") (pinfunction "-_1") (pintype "bidirectional"))
      (node (ref "J2") (pin "NC1") (pinfunction "PAD1_NC1") (pintype "bidirectional"))
      (node (ref "J2") (pin "NC2") (pinfunction "PAD2_NC2") (pintype "bidirectional"))
      (node (ref "J3") (pin "2") (pinfunction "2_2") (pintype "passive"))
      (node (ref "J3") (pin "6") (pinfunction "6_6") (pintype "passive"))
      (node (ref "J3") (pin "7") (pinfunction "7_7") (pintype "passive"))
      (node (ref "J5") (pin "1") (pinfunction "1_1") (pintype "passive"))
      (node (ref "LDO1") (pin "2") (pinfunction "GND_2") (pintype "passive"))
      (node (ref "LDO1") (pin "4") (pinfunction "GND_2_4") (pintype "passive"))
      (node (ref "LDO2") (pin "2") (pinfunction "GND_2") (pintype "passive"))
      (node (ref "LDO2") (pin "4") (pinfunction "GND_2_4") (pintype "passive"))
      (node (ref "LDO3") (pin "2") (pinfunction "GND_2") (pintype "passive"))
      (node (ref "LDO3") (pin "4") (pinfunction "GND_2_4") (pintype "passive"))
      (node (ref "PAD10") (pin "1") (pinfunction "P_1") (pintype "passive"))
      (node (ref "Q1") (pin "2") (pinfunction "S_2") (pintype "passive"))
      (node (ref "Q2") (pin "2") (pinfunction "S_2") (pintype "bidirectional"))
      (node (ref "Q3") (pin "2") (pinfunction "S_2") (pintype "passive"))
      (node (ref "Q5") (pin "2") (pinfunction "S_2") (pintype "passive"))
      (node (ref "R1") (pin "2") (pinfunction "2_2") (pintype "passive"))
      (node (ref "R15") (pin "1") (pinfunction "1_1") (pintype "passive"))
      (node (ref "R17") (pin "1") (pinfunction "1_1") (pintype "passive"))
      (node (ref "R18") (pin "1") (pinfunction "1_1") (pintype "passive"))
      (node (ref "R23") (pin "1") (pinfunction "1_1") (pintype "passive"))
      (node (ref "R24") (pin "1") (pinfunction "1_1") (pintype "passive"))
      (node (ref "R5") (pin "1") (pinfunction "1_1") (pintype "passive"))
      (node (ref "R6") (pin "1") (pinfunction "1_1") (pintype "passive"))
      (node (ref "R8") (pin "1") (pinfunction "1_1") (pintype "passive"))
      (node (ref "R9") (pin "1") (pinfunction "1_1") (pintype "passive"))
      (node (ref "S1") (pin "P1") (pinfunction "1_P1") (pintype "bidirectional"))
      (node (ref "S1") (pin "P4") (pinfunction "1_P4") (pintype "bidirectional"))
      (node (ref "U$2") (pin "P2") (pinfunction "GND_P2") (pintype "bidirectional"))
      (node (ref "U$2") (pin "P4") (pinfunction "GND_P4") (pintype "bidirectional"))
      (node (ref "U1") (pin "2") (pinfunction "GNDN2_2") (pintype "bidirectional"))
      (node (ref "U1") (pin "27") (pinfunction "GNDN1_27") (pintype "bidirectional"))
      (node (ref "U1") (pin "28") (pinfunction "N/C_28") (pintype "bidirectional"))
      (node (ref "U1") (pin "4") (pinfunction "GNDN3_4") (pintype "bidirectional"))
      (node (ref "U1") (pin "6") (pinfunction "GNDN4_6") (pintype "bidirectional"))
      (node (ref "U1") (pin "PAD") (pinfunction "PAD_PAD") (pintype "bidirectional"))
      (node (ref "U2") (pin "12") (pinfunction "VSSA/VREF-_12") (pintype "bidirectional"))
      (node (ref "U2") (pin "18") (pinfunction "VSS_18") (pintype "bidirectional"))
      (node (ref "U2") (pin "31") (pinfunction "VSS_1_31") (pintype "bidirectional"))
      (node (ref "U2") (pin "47") (pinfunction "VSS_2_47") (pintype "bidirectional"))
      (node (ref "U2") (pin "63") (pinfunction "VSS_3_63") (pintype "bidirectional"))
      (node (ref "U3") (pin "2") (pinfunction "GND_2") (pintype "bidirectional"))
      (node (ref "U4") (pin "2") (pinfunction "ADDR_2") (pintype "input"))
      (node (ref "U4") (pin "3") (pinfunction "GND_3") (pintype "power_in"))
      (node (ref "U4") (pin "7") (pinfunction "EXP_7") (pintype "power_in"))
      (node (ref "U5") (pin "2") (pinfunction "GND_2") (pintype "passive"))
      (node (ref "U5") (pin "4") (pinfunction "ADD0_4") (pintype "input"))
    )
    (net (code "20") (name "HEART") (class "Default")
      (node (ref "D4") (pin "C") (pinfunction "C_C") (pintype "passive"))
      (node (ref "U2") (pin "2") (pinfunction "PC13_2") (pintype "bidirectional"))
    )
    (net (code "21") (name "I2C1_SCL") (class "Default")
      (node (ref "U2") (pin "61") (pinfunction "PB8_61") (pintype "bidirectional"))
      (node (ref "U3") (pin "6") (pinfunction "SCL_6") (pintype "bidirectional"))
      (node (ref "U4") (pin "4") (pinfunction "SCL_4") (pintype "input"))
      (node (ref "U5") (pin "1") (pinfunction "SCL_1") (pintype "input"))
    )
    (net (code "22") (name "I2C1_SDA") (class "Default")
      (node (ref "U2") (pin "62") (pinfunction "PB9_62") (pintype "bidirectional"))
      (node (ref "U3") (pin "1") (pinfunction "SDA_1") (pintype "bidirectional"))
      (node (ref "U4") (pin "6") (pinfunction "SDA_6") (pintype "bidirectional"))
      (node (ref "U5") (pin "6") (pinfunction "SDA_6") (pintype "bidirectional"))
    )
    (net (code "23") (name "I2C2_SCL") (class "Default")
      (node (ref "U2") (pin "29") (pinfunction "PB10_29") (pintype "bidirectional"))
    )
    (net (code "24") (name "I2C2_SDA") (class "Default")
      (node (ref "U2") (pin "30") (pinfunction "PB11_30") (pintype "bidirectional"))
    )
    (net (code "25") (name "I2C3_SCL") (class "Default")
      (node (ref "U2") (pin "8") (pinfunction "PC0_8") (pintype "bidirectional"))
    )
    (net (code "26") (name "I2C3_SDA") (class "Default")
      (node (ref "U2") (pin "9") (pinfunction "PC1_9") (pintype "bidirectional"))
    )
    (net (code "27") (name "I2C4_SCL") (class "Default")
      (node (ref "INA1") (pin "5") (pinfunction "SCL_5") (pintype "bidirectional"))
      (node (ref "R29") (pin "1") (pinfunction "1_1") (pintype "passive"))
      (node (ref "U2") (pin "58") (pinfunction "PB6_58") (pintype "bidirectional"))
    )
    (net (code "28") (name "I2C4_SDA") (class "Default")
      (node (ref "INA1") (pin "4") (pinfunction "SDA_4") (pintype "bidirectional"))
      (node (ref "R28") (pin "1") (pinfunction "1_1") (pintype "passive"))
      (node (ref "U2") (pin "59") (pinfunction "PB7_59") (pintype "bidirectional"))
    )
    (net (code "29") (name "ICSP") (class "Default")
      (node (ref "J5") (pin "2") (pinfunction "2_2") (pintype "passive"))
      (node (ref "U1") (pin "18") (pinfunction "ICSP_18") (pintype "bidirectional"))
    )
    (net (code "30") (name "ICSPCLK") (class "Default")
      (node (ref "J5") (pin "4") (pinfunction "4_4") (pintype "passive"))
      (node (ref "U1") (pin "10") (pinfunction "P3/ICSPCLK_10") (pintype "bidirectional"))
    )
    (net (code "31") (name "ICSPDAT") (class "Default")
      (node (ref "J5") (pin "5") (pinfunction "5_5") (pintype "passive"))
      (node (ref "U1") (pin "11") (pinfunction "P5/ICSPDAT_11") (pintype "bidirectional"))
    )
    (net (code "32") (name "LED_20") (class "Default")
      (node (ref "D9") (pin "C") (pinfunction "C_C") (pintype "passive"))
    )
    (net (code "33") (name "LED_40") (class "Default")
      (node (ref "D8") (pin "C") (pinfunction "C_C") (pintype "passive"))
    )
    (net (code "34") (name "LED_60") (class "Default")
      (node (ref "D7") (pin "C") (pinfunction "C_C") (pintype "passive"))
    )
    (net (code "35") (name "LED_80") (class "Default")
      (node (ref "D6") (pin "C") (pinfunction "C_C") (pintype "passive"))
    )
    (net (code "36") (name "LED_100") (class "Default")
      (node (ref "D5") (pin "C") (pinfunction "C_C") (pintype "passive"))
    )
    (net (code "37") (name "LO2") (class "Default")
      (node (ref "U2") (pin "15") (pinfunction "PA1_15") (pintype "bidirectional"))
    )
    (net (code "38") (name "LOADLOW") (class "Default")
      (node (ref "U1") (pin "13") (pinfunction "P1_13") (pintype "bidirectional"))
    )
    (net (code "39") (name "LX") (class "Default")
      (node (ref "L2") (pin "2") (pinfunction "2_2") (pintype "passive"))
      (node (ref "U1") (pin "1") (pinfunction "LXN2_1") (pintype "bidirectional"))
      (node (ref "U1") (pin "23") (pinfunction "LXP2_23") (pintype "bidirectional"))
      (node (ref "U1") (pin "25") (pinfunction "LXP1_25") (pintype "bidirectional"))
      (node (ref "U1") (pin "26") (pinfunction "LXN1_26") (pintype "bidirectional"))
      (node (ref "U1") (pin "3") (pinfunction "LXN3_3") (pintype "bidirectional"))
      (node (ref "U1") (pin "5") (pinfunction "LXN4_5") (pintype "bidirectional"))
    )
    (net (code "40") (name "LX2") (class "Default")
      (node (ref "D1") (pin "2") (pinfunction "A_2") (pintype "passive"))
      (node (ref "L1") (pin "2") (pinfunction "2_2") (pintype "passive"))
      (node (ref "Q2") (pin "3") (pinfunction "D_3") (pintype "bidirectional"))
    )
    (net (code "41") (name "NEO_BAT") (class "Default")
      (node (ref "PAD8") (pin "1") (pinfunction "P_1") (pintype "passive"))
      (node (ref "Q6") (pin "3") (pinfunction "D_3") (pintype "passive"))
    )
    (net (code "42") (name "NEO_ENABLE") (class "Default")
      (node (ref "R21") (pin "2") (pinfunction "2_2") (pintype "passive"))
    )
    (net (code "43") (name "NEO_TIM") (class "Default")
      (node (ref "PAD9") (pin "1") (pinfunction "P_1") (pintype "passive"))
    )
    (net (code "44") (name "NRST") (class "Default")
      (node (ref "C30") (pin "1") (pinfunction "1_1") (pintype "passive"))
      (node (ref "S1") (pin "P2") (pinfunction "2_P2") (pintype "bidirectional"))
      (node (ref "S1") (pin "P3") (pinfunction "2_P3") (pintype "bidirectional"))
      (node (ref "U2") (pin "7") (pinfunction "NRST_7") (pintype "bidirectional"))
    )
    (net (code "45") (name "Net-(CHR1-ISET)") (class "Default")
      (node (ref "CHR1") (pin "2") (pinfunction "ISET_2") (pintype "input"))
      (node (ref "R8") (pin "2") (pinfunction "2_2") (pintype "passive"))
    )
    (net (code "46") (name "Net-(CHR1-PRETERM)") (class "Default")
      (node (ref "CHR1") (pin "4") (pinfunction "PRETERM_4") (pintype "input"))
      (node (ref "R9") (pin "2") (pinfunction "2_2") (pintype "passive"))
    )
    (net (code "47") (name "Net-(CHR1-TS)") (class "Default")
      (node (ref "CHR1") (pin "9") (pinfunction "TS_9") (pintype "input"))
      (node (ref "R5") (pin "2") (pinfunction "2_2") (pintype "passive"))
    )
    (net (code "48") (name "Net-(CHR1-~{CHG})") (class "Default")
      (node (ref "CHR1") (pin "8") (pinfunction "~{CHG}_8") (pintype "output"))
      (node (ref "D2") (pin "C") (pinfunction "C_C") (pintype "passive"))
    )
    (net (code "49") (name "Net-(CHR1-~{PG})") (class "Default")
      (node (ref "CHR1") (pin "5") (pinfunction "~{PG}_5") (pintype "output"))
      (node (ref "D3") (pin "C") (pinfunction "C_C") (pintype "passive"))
    )
    (net (code "50") (name "Net-(D2-PadA)") (class "Default")
      (node (ref "D2") (pin "A") (pinfunction "A_A") (pintype "passive"))
      (node (ref "R4") (pin "1") (pinfunction "1_1") (pintype "passive"))
    )
    (net (code "51") (name "Net-(D3-PadA)") (class "Default")
      (node (ref "D3") (pin "A") (pinfunction "A_A") (pintype "passive"))
      (node (ref "R10") (pin "1") (pinfunction "1_1") (pintype "passive"))
    )
    (net (code "52") (name "Net-(D4-PadA)") (class "Default")
      (node (ref "D4") (pin "A") (pinfunction "A_A") (pintype "passive"))
      (node (ref "R11") (pin "2") (pinfunction "2_2") (pintype "passive"))
    )
    (net (code "53") (name "Net-(D5-PadA)") (class "Default")
      (node (ref "D5") (pin "A") (pinfunction "A_A") (pintype "passive"))
      (node (ref "R30") (pin "2") (pinfunction "2_2") (pintype "passive"))
    )
    (net (code "54") (name "Net-(D6-PadA)") (class "Default")
      (node (ref "D6") (pin "A") (pinfunction "A_A") (pintype "passive"))
      (node (ref "R31") (pin "2") (pinfunction "2_2") (pintype "passive"))
    )
    (net (code "55") (name "Net-(D7-PadA)") (class "Default")
      (node (ref "D7") (pin "A") (pinfunction "A_A") (pintype "passive"))
      (node (ref "R32") (pin "2") (pinfunction "2_2") (pintype "passive"))
    )
    (net (code "56") (name "Net-(D8-PadA)") (class "Default")
      (node (ref "D8") (pin "A") (pinfunction "A_A") (pintype "passive"))
      (node (ref "R33") (pin "2") (pinfunction "2_2") (pintype "passive"))
    )
    (net (code "57") (name "Net-(D9-PadA)") (class "Default")
      (node (ref "D9") (pin "A") (pinfunction "A_A") (pintype "passive"))
      (node (ref "R34") (pin "2") (pinfunction "2_2") (pintype "passive"))
    )
    (net (code "58") (name "Net-(INA1-VBUS)") (class "Default")
      (node (ref "C38") (pin "2") (pinfunction "2_2") (pintype "passive"))
      (node (ref "INA1") (pin "8") (pinfunction "VBUS_8") (pintype "bidirectional"))
      (node (ref "INA1") (pin "9") (pinfunction "VIN-_9") (pintype "bidirectional"))
      (node (ref "R26") (pin "1") (pinfunction "1_1") (pintype "passive"))
    )
    (net (code "59") (name "Net-(INA1-VIN+)") (class "Default")
      (node (ref "C38") (pin "1") (pinfunction "1_1") (pintype "passive"))
      (node (ref "INA1") (pin "10") (pinfunction "VIN+_10") (pintype "bidirectional"))
      (node (ref "R25") (pin "1") (pinfunction "1_1") (pintype "passive"))
    )
    (net (code "60") (name "Net-(J1-CARD_DET1)") (class "Default")
      (node (ref "J1") (pin "9") (pinfunction "CARD_DET1_9") (pintype "passive"))
      (node (ref "R3") (pin "1") (pinfunction "1_1") (pintype "passive"))
    )
    (net (code "61") (name "Net-(J2-+)") (class "Default")
      (node (ref "J2") (pin "2") (pinfunction "+_2") (pintype "bidirectional"))
      (node (ref "R7") (pin "2") (pinfunction "2_2") (pintype "passive"))
    )
    (net (code "62") (name "Net-(OSC1-P$1)") (class "Default")
      (node (ref "C12") (pin "1") (pinfunction "1_1") (pintype "passive"))
      (node (ref "OSC1") (pin "P1") (pinfunction "P$1_P1") (pintype "bidirectional"))
      (node (ref "U2") (pin "3") (pinfunction "PC14-OSC_IN_3") (pintype "bidirectional"))
    )
    (net (code "63") (name "Net-(OSC1-P$2)") (class "Default")
      (node (ref "C11") (pin "1") (pinfunction "1_1") (pintype "passive"))
      (node (ref "OSC1") (pin "P2") (pinfunction "P$2_P2") (pintype "bidirectional"))
      (node (ref "U2") (pin "4") (pinfunction "PC15-OSC32_OUT_4") (pintype "bidirectional"))
    )
    (net (code "64") (name "Net-(Q1-D)") (class "Default")
      (node (ref "Q1") (pin "3") (pinfunction "D_3") (pintype "passive"))
      (node (ref "R14") (pin "1") (pinfunction "1_1") (pintype "passive"))
    )
    (net (code "65") (name "Net-(Q1-G)") (class "Default")
      (node (ref "Q1") (pin "1") (pinfunction "G_1") (pintype "passive"))
      (node (ref "R15") (pin "2") (pinfunction "2_2") (pintype "passive"))
      (node (ref "R16") (pin "1") (pinfunction "1_1") (pintype "passive"))
    )
    (net (code "66") (name "Net-(Q3-D)") (class "Default")
      (node (ref "Q3") (pin "3") (pinfunction "D_3") (pintype "passive"))
      (node (ref "Q4") (pin "1") (pinfunction "G_1") (pintype "passive"))
      (node (ref "R20") (pin "1") (pinfunction "1_1") (pintype "passive"))
    )
    (net (code "67") (name "Net-(Q3-G)") (class "Default")
      (node (ref "Q3") (pin "1") (pinfunction "G_1") (pintype "passive"))
      (node (ref "R18") (pin "2") (pinfunction "2_2") (pintype "passive"))
      (node (ref "R19") (pin "1") (pinfunction "1_1") (pintype "passive"))
    )
    (net (code "68") (name "Net-(Q5-D)") (class "Default")
      (node (ref "Q5") (pin "3") (pinfunction "D_3") (pintype "passive"))
      (node (ref "Q6") (pin "1") (pinfunction "G_1") (pintype "passive"))
      (node (ref "R22") (pin "1") (pinfunction "1_1") (pintype "passive"))
    )
    (net (code "69") (name "Net-(Q5-G)") (class "Default")
      (node (ref "Q5") (pin "1") (pinfunction "G_1") (pintype "passive"))
      (node (ref "R21") (pin "1") (pinfunction "1_1") (pintype "passive"))
      (node (ref "R6") (pin "2") (pinfunction "2_2") (pintype "passive"))
    )
    (net (code "70") (name "Net-(R12-Pad2)") (class "Default")
      (node (ref "R12") (pin "2") (pinfunction "2_2") (pintype "passive"))
      (node (ref "S2") (pin "P2") (pinfunction "2_P2") (pintype "bidirectional"))
      (node (ref "S2") (pin "P3") (pinfunction "2_P3") (pintype "bidirectional"))
    )
    (net (code "71") (name "Net-(U$2-P$1)") (class "Default")
      (node (ref "C10") (pin "1") (pinfunction "1_1") (pintype "passive"))
      (node (ref "U$2") (pin "P1") (pinfunction "P$1_P1") (pintype "bidirectional"))
      (node (ref "U2") (pin "5") (pinfunction "PH0-OSC_IN_5") (pintype "bidirectional"))
    )
    (net (code "72") (name "Net-(U$2-P$2)") (class "Default")
      (node (ref "C9") (pin "1") (pinfunction "1_1") (pintype "passive"))
      (node (ref "U$2") (pin "P3") (pinfunction "P$2_P3") (pintype "bidirectional"))
      (node (ref "U2") (pin "6") (pinfunction "PH1-OSC_OUT_6") (pintype "bidirectional"))
    )
    (net (code "73") (name "Net-(U1-FBSOL)") (class "Default")
      (node (ref "C3") (pin "1") (pinfunction "1_1") (pintype "passive"))
      (node (ref "R2") (pin "2") (pinfunction "2_2") (pintype "passive"))
      (node (ref "U1") (pin "9") (pinfunction "FBSOL_9") (pintype "bidirectional"))
    )
    (net (code "74") (name "Net-(U1-VCORE)") (class "Default")
      (node (ref "C2") (pin "1") (pinfunction "1_1") (pintype "passive"))
      (node (ref "U1") (pin "15") (pinfunction "VCORE_15") (pintype "bidirectional"))
    )
    (net (code "75") (name "PB5") (class "Default")
      (node (ref "U2") (pin "57") (pinfunction "PB5_57") (pintype "bidirectional"))
    )
    (net (code "76") (name "PH3BOOT") (class "Default")
      (node (ref "R12") (pin "1") (pinfunction "1_1") (pintype "passive"))
      (node (ref "R17") (pin "2") (pinfunction "2_2") (pintype "passive"))
      (node (ref "U2") (pin "60") (pinfunction "PH3-BOOT0_60") (pintype "bidirectional"))
    )
    (net (code "77") (name "PWM") (class "Default")
      (node (ref "Q2") (pin "1") (pinfunction "G_1") (pintype "bidirectional"))
      (node (ref "U1") (pin "12") (pinfunction "P0_12") (pintype "bidirectional"))
      (node (ref "U1") (pin "19") (pinfunction "P6/SCLK_19") (pintype "bidirectional"))
    )
    (net (code "78") (name "RO1") (class "Default")
      (node (ref "U2") (pin "38") (pinfunction "PC7_38") (pintype "bidirectional"))
    )
    (net (code "79") (name "RO2") (class "Default")
      (node (ref "U2") (pin "41") (pinfunction "PA8_41") (pintype "bidirectional"))
    )
    (net (code "80") (name "SD_CARD_EN") (class "Default")
      (node (ref "LDO2") (pin "3") (pinfunction "EN_3") (pintype "input"))
      (node (ref "U2") (pin "50") (pinfunction "PA15_50") (pintype "bidirectional"))
    )
    (net (code "81") (name "SD_CLK") (class "Default")
      (node (ref "J1") (pin "5") (pinfunction "CLK_5") (pintype "input"))
      (node (ref "U2") (pin "53") (pinfunction "PC12_53") (pintype "bidirectional"))
    )
    (net (code "82") (name "SD_CMD") (class "Default")
      (node (ref "J1") (pin "3") (pinfunction "CMD_3") (pintype "input"))
      (node (ref "U2") (pin "54") (pinfunction "PD2_54") (pintype "bidirectional"))
    )
    (net (code "83") (name "SD_D0") (class "Default")
      (node (ref "J1") (pin "7") (pinfunction "DAT0_7") (pintype "bidirectional"))
      (node (ref "U2") (pin "39") (pinfunction "PC8_39") (pintype "bidirectional"))
    )
    (net (code "84") (name "SD_D1") (class "Default")
      (node (ref "J1") (pin "8") (pinfunction "DAT1_8") (pintype "bidirectional"))
      (node (ref "U2") (pin "40") (pinfunction "PC9_40") (pintype "bidirectional"))
    )
    (net (code "85") (name "SD_D2") (class "Default")
      (node (ref "J1") (pin "1") (pinfunction "DAT2_1") (pintype "bidirectional"))
      (node (ref "U2") (pin "51") (pinfunction "PC10_51") (pintype "bidirectional"))
    )
    (net (code "86") (name "SD_D3") (class "Default")
      (node (ref "J1") (pin "2") (pinfunction "CD/DAT3_2") (pintype "bidirectional"))
      (node (ref "U2") (pin "52") (pinfunction "PC11_52") (pintype "bidirectional"))
    )
    (net (code "87") (name "SD_DET") (class "Default")
      (node (ref "R3") (pin "2") (pinfunction "2_2") (pintype "passive"))
      (node (ref "U2") (pin "56") (pinfunction "PB4_56") (pintype "bidirectional"))
    )
    (net (code "88") (name "SENS_EN") (class "Default")
      (node (ref "LDO3") (pin "3") (pinfunction "EN_3") (pintype "input"))
    )
    (net (code "89") (name "SOL+") (class "Default")
      (node (ref "C4") (pin "1") (pinfunction "1_1") (pintype "passive"))
      (node (ref "C5") (pin "1") (pinfunction "1_1") (pintype "passive"))
      (node (ref "C6") (pin "2") (pinfunction "2_2") (pintype "passive"))
      (node (ref "L1") (pin "1") (pinfunction "1_1") (pintype "passive"))
      (node (ref "L2") (pin "1") (pinfunction "1_1") (pintype "passive"))
      (node (ref "R2") (pin "1") (pinfunction "1_1") (pintype "passive"))
    )
    (net (code "90") (name "SPI1_CS1") (class "Default")
      (node (ref "U2") (pin "24") (pinfunction "PC4_24") (pintype "bidirectional"))
    )
    (net (code "91") (name "SPI1_MOSI") (class "Default")
      (node (ref "U2") (pin "23") (pinfunction "PA7_23") (pintype "bidirectional"))
    )
    (net (code "92") (name "SPI1_SCK") (class "Default")
      (node (ref "U2") (pin "21") (pinfunction "PA5_21") (pintype "bidirectional"))
    )
    (net (code "93") (name "SPI2_CS1") (class "Default")
      (node (ref "U2") (pin "33") (pinfunction "PB12_33") (pintype "bidirectional"))
    )
    (net (code "94") (name "SPI2_CS2_OUT") (class "Default")
      (node (ref "U2") (pin "37") (pinfunction "PC6_37") (pintype "bidirectional"))
    )
    (net (code "95") (name "SPI2_MISO") (class "Default")
      (node (ref "U2") (pin "35") (pinfunction "PB14_35") (pintype "bidirectional"))
    )
    (net (code "96") (name "SPI2_MOSI") (class "Default")
      (node (ref "U2") (pin "36") (pinfunction "PB15_36") (pintype "bidirectional"))
    )
    (net (code "97") (name "SPI2_SCK") (class "Default")
      (node (ref "U2") (pin "34") (pinfunction "PB13_34") (pintype "bidirectional"))
    )
    (net (code "98") (name "SWCLK") (class "Default")
      (node (ref "U2") (pin "49") (pinfunction "PA14_49") (pintype "bidirectional"))
    )
    (net (code "99") (name "SWDIO") (class "Default")
      (node (ref "U2") (pin "46") (pinfunction "PA13_46") (pintype "bidirectional"))
    )
    (net (code "100") (name "SWO") (class "Default")
      (node (ref "U2") (pin "55") (pinfunction "PB3_55") (pintype "bidirectional"))
    )
    (net (code "101") (name "UART_RX") (class "Default")
      (node (ref "U2") (pin "43") (pinfunction "PA10_43") (pintype "bidirectional"))
    )
    (net (code "102") (name "UART_TX") (class "Default")
      (node (ref "U2") (pin "42") (pinfunction "PA9_42") (pintype "bidirectional"))
    )
    (net (code "103") (name "USB_DM") (class "Default")
      (node (ref "U2") (pin "44") (pinfunction "PA11_44") (pintype "bidirectional"))
    )
    (net (code "104") (name "USB_DP") (class "Default")
      (node (ref "U2") (pin "45") (pinfunction "PA12_45") (pintype "bidirectional"))
    )
    (net (code "105") (name "VBAT") (class "Default")
      (node (ref "C27") (pin "1") (pinfunction "1_1") (pintype "passive"))
      (node (ref "C34") (pin "1") (pinfunction "1_1") (pintype "passive"))
      (node (ref "C36") (pin "2") (pinfunction "2_2") (pintype "passive"))
      (node (ref "C42") (pin "1") (pinfunction "1_1") (pintype "passive"))
      (node (ref "CHR1") (pin "10") (pinfunction "OUT_10") (pintype "output"))
      (node (ref "J5") (pin "3") (pinfunction "3_3") (pintype "passive"))
      (node (ref "LDO1") (pin "1") (pinfunction "IN_1") (pintype "input"))
      (node (ref "LDO1") (pin "3") (pinfunction "EN_3") (pintype "input"))
      (node (ref "LDO2") (pin "1") (pinfunction "IN_1") (pintype "input"))
      (node (ref "LDO3") (pin "1") (pinfunction "IN_1") (pintype "input"))
      (node (ref "Q4") (pin "2") (pinfunction "S_2") (pintype "passive"))
      (node (ref "Q6") (pin "2") (pinfunction "S_2") (pintype "passive"))
      (node (ref "R13") (pin "2") (pinfunction "2_2") (pintype "passive"))
      (node (ref "R20") (pin "2") (pinfunction "2_2") (pintype "passive"))
      (node (ref "R22") (pin "2") (pinfunction "2_2") (pintype "passive"))
      (node (ref "R26") (pin "2") (pinfunction "2_2") (pintype "passive"))
      (node (ref "R27") (pin "1") (pinfunction "1_1") (pintype "passive"))
      (node (ref "R4") (pin "2") (pinfunction "2_2") (pintype "passive"))
      (node (ref "R7") (pin "1") (pinfunction "1_1") (pintype "passive"))
    )
    (net (code "106") (name "VBAT_SENSE") (class "Default")
      (node (ref "C37") (pin "1") (pinfunction "1_1") (pintype "passive"))
      (node (ref "R13") (pin "1") (pinfunction "1_1") (pintype "passive"))
      (node (ref "R14") (pin "2") (pinfunction "2_2") (pintype "passive"))
      (node (ref "R16") (pin "2") (pinfunction "2_2") (pintype "passive"))
      (node (ref "U2") (pin "10") (pinfunction "PC2_10") (pintype "bidirectional"))
    )
    (net (code "107") (name "VBUS") (class "Default")
      (node (ref "C35") (pin "2") (pinfunction "2_2") (pintype "passive"))
      (node (ref "CHR1") (pin "1") (pinfunction "IN_1") (pintype "power_in"))
    )
    (net (code "108") (name "VCC") (class "Default")
      (node (ref "C1") (pin "1") (pinfunction "1_1") (pintype "passive"))
      (node (ref "C7") (pin "1") (pinfunction "1_1") (pintype "passive"))
      (node (ref "C8") (pin "1") (pinfunction "1_1") (pintype "passive"))
      (node (ref "D1") (pin "1") (pinfunction "C_1") (pintype "passive"))
      (node (ref "R25") (pin "2") (pinfunction "2_2") (pintype "passive"))
      (node (ref "R27") (pin "2") (pinfunction "2_2") (pintype "passive"))
      (node (ref "U1") (pin "16") (pinfunction "VCCIO_16") (pintype "bidirectional"))
      (node (ref "U1") (pin "21") (pinfunction "VCC_21") (pintype "bidirectional"))
      (node (ref "U1") (pin "22") (pinfunction "VBAT2_22") (pintype "bidirectional"))
      (node (ref "U1") (pin "24") (pinfunction "VBAT1_24") (pintype "bidirectional"))
    )
    (net (code "109") (name "VDDA") (class "Default")
      (node (ref "C14") (pin "1") (pinfunction "1_1") (pintype "passive"))
      (node (ref "L3") (pin "1") (pinfunction "1_1") (pintype "passive"))
      (node (ref "U2") (pin "13") (pinfunction "VDDA/VREF+_13") (pintype "bidirectional"))
    )
    (net (code "110") (name "unconnected-(CHR1-NC-Pad6)") (class "Default")
      (node (ref "CHR1") (pin "6") (pinfunction "NC_6") (pintype "no_connect"))
    )
    (net (code "111") (name "unconnected-(INA1-ALERT-Pad3)") (class "Default")
      (node (ref "INA1") (pin "3") (pinfunction "ALERT_3") (pintype "bidirectional"))
    )
    (net (code "112") (name "unconnected-(U1-P2-Pad14)") (class "Default")
      (node (ref "U1") (pin "14") (pinfunction "P2_14") (pintype "bidirectional"))
    )
    (net (code "113") (name "unconnected-(U1-P4-Pad17)") (class "Default")
      (node (ref "U1") (pin "17") (pinfunction "P4_17") (pintype "bidirectional"))
    )
    (net (code "114") (name "unconnected-(U1-P7{slash}SOUT-Pad20)") (class "Default")
      (node (ref "U1") (pin "20") (pinfunction "P7/SOUT_20") (pintype "bidirectional"))
    )
    (net (code "115") (name "unconnected-(U4-INT-Pad5)") (class "Default")
      (node (ref "U4") (pin "5") (pinfunction "INT_5") (pintype "output"))
    )
    (net (code "116") (name "unconnected-(U5-ALERT-Pad3)") (class "Default")
      (node (ref "U5") (pin "3") (pinfunction "ALERT_3") (pintype "input"))
    )
  )
)
